# Timelapse.net
KiCad netlist of a schematic drawn in EAGLE
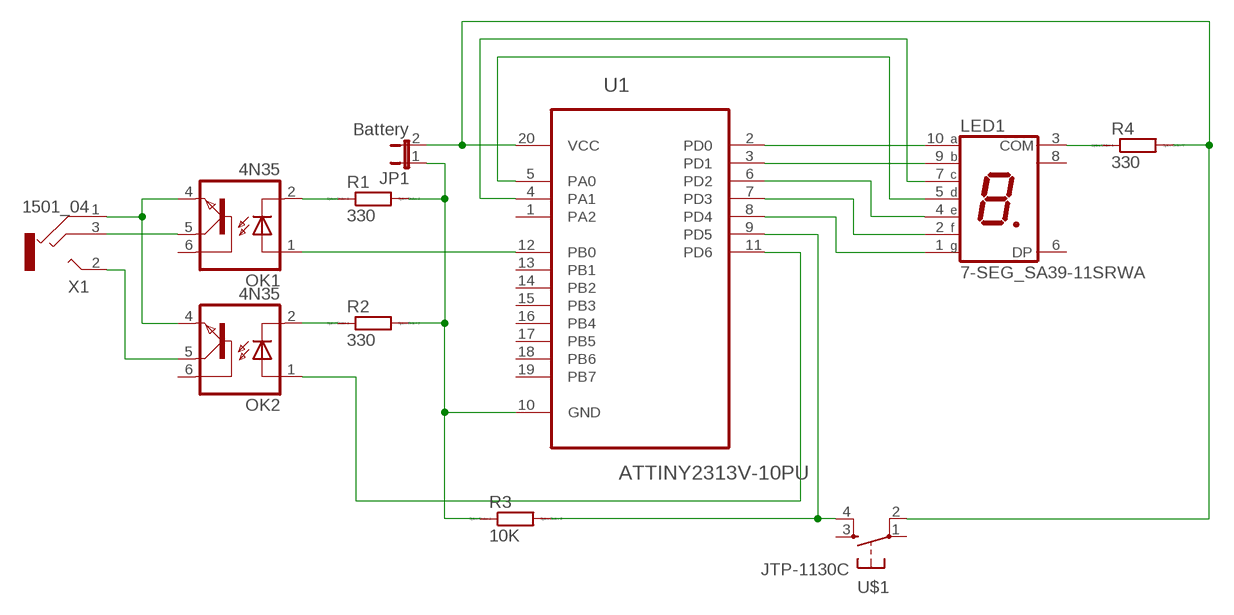
[diagram p0: schematic, sheet 1]

(export (version "E")
  (design (tool "Eeschema 10.0.6"))
  (components
    (comp (ref "JP1")
      (value "Battery")
      (footprint "eagle-import:JP1")
      (libsource (lib "eagle-import") (part "JP1E"))
    )
    (comp (ref "LED1")
      (value "7-SEG_SA39-11SRWA")
      (footprint "eagle-import:SA39-11SRWA")
      (libsource (lib "eagle-import") (part "7-SEG_SA39-11SRWA"))
    )
    (comp (ref "OK1")
      (value "4N35")
      (footprint "eagle-import:DIL06")
      (fields (field (name "MF") "FAIRCHILD SEMICONDUCTOR"))
      (libsource (lib "eagle-import") (part "4N35"))
    )
    (comp (ref "OK2")
      (value "4N35")
      (footprint "eagle-import:DIL06")
      (fields (field (name "MF") "FAIRCHILD SEMICONDUCTOR"))
      (libsource (lib "eagle-import") (part "4N35"))
    )
    (comp (ref "R1")
      (value "330")
      (footprint "eagle-import:0204_7")
      (libsource (lib "eagle-import") (part "R0204/7"))
    )
    (comp (ref "R2")
      (value "330")
      (footprint "eagle-import:0204_7")
      (libsource (lib "eagle-import") (part "R0204/7"))
    )
    (comp (ref "R3")
      (value "10K")
      (footprint "eagle-import:0204_7")
      (libsource (lib "eagle-import") (part "R0204/7"))
    )
    (comp (ref "R4")
      (value "330")
      (footprint "eagle-import:0204_7")
      (libsource (lib "eagle-import") (part "R0204/7"))
    )
    (comp (ref "U$1")
      (value "JTP-1130C")
      (footprint "eagle-import:JTP-1130")
      (libsource (lib "eagle-import") (part "JTP-1130C"))
    )
    (comp (ref "U1")
      (value "ATTINY2313V-10PU")
      (footprint "eagle-import:DIP254P762X533-20")
      (libsource (lib "eagle-import") (part "ATTINY2313V-10PU"))
    )
    (comp (ref "X1")
      (value "1501_04")
      (footprint "eagle-import:1501_05")
      (libsource (lib "eagle-import") (part "1501_04"))
    )
  )
  (nets
    (net (code "1") (name "Net-(LED1-A)") (class "Default")
      (node (ref "LED1") (pin "10") (pinfunction "A_10") (pintype "passive"))
      (node (ref "U1") (pin "2") (pinfunction "PD0_2") (pintype "bidirectional"))
    )
    (net (code "2") (name "Net-(LED1-B)") (class "Default")
      (node (ref "LED1") (pin "9") (pinfunction "B_9") (pintype "passive"))
      (node (ref "U1") (pin "3") (pinfunction "PD1_3") (pintype "bidirectional"))
    )
    (net (code "3") (name "Net-(LED1-C)") (class "Default")
      (node (ref "LED1") (pin "7") (pinfunction "C_7") (pintype "passive"))
      (node (ref "U1") (pin "4") (pinfunction "PA1_4") (pintype "bidirectional"))
    )
    (net (code "4") (name "Net-(LED1-COM-Pad3)") (class "Default")
      (node (ref "LED1") (pin "3") (pinfunction "COM_3") (pintype "passive"))
      (node (ref "R4") (pin "1") (pinfunction "1_1") (pintype "passive"))
    )
    (net (code "5") (name "Net-(LED1-D)") (class "Default")
      (node (ref "LED1") (pin "5") (pinfunction "D_5") (pintype "passive"))
      (node (ref "U1") (pin "5") (pinfunction "PA0_5") (pintype "bidirectional"))
    )
    (net (code "6") (name "Net-(LED1-E)") (class "Default")
      (node (ref "LED1") (pin "4") (pinfunction "E_4") (pintype "passive"))
      (node (ref "U1") (pin "6") (pinfunction "PD2_6") (pintype "bidirectional"))
    )
    (net (code "7") (name "Net-(LED1-F)") (class "Default")
      (node (ref "LED1") (pin "2") (pinfunction "F_2") (pintype "passive"))
      (node (ref "U1") (pin "7") (pinfunction "PD3_7") (pintype "bidirectional"))
    )
    (net (code "8") (name "Net-(LED1-G)") (class "Default")
      (node (ref "LED1") (pin "1") (pinfunction "G_1") (pintype "passive"))
      (node (ref "U1") (pin "8") (pinfunction "PD4_8") (pintype "bidirectional"))
    )
    (net (code "9") (name "Net-(OK1-A)") (class "Default")
      (node (ref "OK1") (pin "1") (pinfunction "A_1") (pintype "passive"))
      (node (ref "U1") (pin "12") (pinfunction "PB0_12") (pintype "bidirectional"))
    )
    (net (code "10") (name "Net-(OK1-C)") (class "Default")
      (node (ref "OK1") (pin "2") (pinfunction "C_2") (pintype "passive"))
      (node (ref "R1") (pin "1") (pinfunction "1_1") (pintype "passive"))
    )
    (net (code "11") (name "Net-(OK1-COL)") (class "Default")
      (node (ref "OK1") (pin "5") (pinfunction "COL_5") (pintype "passive"))
      (node (ref "X1") (pin "3") (pinfunction "3_3") (pintype "passive"))
    )
    (net (code "12") (name "Net-(OK1-EMI)") (class "Default")
      (node (ref "OK1") (pin "4") (pinfunction "EMI_4") (pintype "passive"))
      (node (ref "OK2") (pin "4") (pinfunction "EMI_4") (pintype "passive"))
      (node (ref "X1") (pin "1") (pinfunction "1_1") (pintype "passive"))
    )
    (net (code "13") (name "Net-(OK2-A)") (class "Default")
      (node (ref "OK2") (pin "1") (pinfunction "A_1") (pintype "passive"))
      (node (ref "U1") (pin "11") (pinfunction "PD6_11") (pintype "bidirectional"))
    )
    (net (code "14") (name "Net-(OK2-C)") (class "Default")
      (node (ref "OK2") (pin "2") (pinfunction "C_2") (pintype "passive"))
      (node (ref "R2") (pin "1") (pinfunction "1_1") (pintype "passive"))
    )
    (net (code "15") (name "Net-(OK2-COL)") (class "Default")
      (node (ref "OK2") (pin "5") (pinfunction "COL_5") (pintype "passive"))
      (node (ref "X1") (pin "2") (pinfunction "2_2") (pintype "passive"))
    )
    (net (code "16") (name "Net-(U$1-P1)") (class "Default")
      (node (ref "JP1") (pin "2") (pinfunction "2_2") (pintype "passive"))
      (node (ref "R4") (pin "2") (pinfunction "2_2") (pintype "passive"))
      (node (ref "U$1") (pin "2") (pinfunction "P1_2") (pintype "passive"))
      (node (ref "U1") (pin "20") (pinfunction "VCC_20") (pintype "power_in"))
    )
    (net (code "17") (name "Net-(U$1-S1)") (class "Default")
      (node (ref "R3") (pin "2") (pinfunction "2_2") (pintype "passive"))
      (node (ref "U$1") (pin "4") (pinfunction "S1_4") (pintype "passive"))
      (node (ref "U1") (pin "9") (pinfunction "PD5_9") (pintype "bidirectional"))
    )
    (net (code "18") (name "Net-(U1-GND)") (class "Default")
      (node (ref "JP1") (pin "1") (pinfunction "1_1") (pintype "passive"))
      (node (ref "R1") (pin "2") (pinfunction "2_2") (pintype "passive"))
      (node (ref "R2") (pin "2") (pinfunction "2_2") (pintype "passive"))
      (node (ref "R3") (pin "1") (pinfunction "1_1") (pintype "passive"))
      (node (ref "U1") (pin "10") (pinfunction "GND_10") (pintype "passive"))
    )
    (net (code "19") (name "unconnected-(LED1-COM-Pad8)") (class "Default")
      (node (ref "LED1") (pin "8") (pinfunction "COM_8") (pintype "passive"))
    )
    (net (code "20") (name "unconnected-(LED1-DP-Pad6)") (class "Default")
      (node (ref "LED1") (pin "6") (pinfunction "DP_6") (pintype "passive"))
    )
    (net (code "21") (name "unconnected-(OK1-BAS-Pad6)") (class "Default")
      (node (ref "OK1") (pin "6") (pinfunction "BAS_6") (pintype "passive"))
    )
    (net (code "22") (name "unconnected-(OK2-BAS-Pad6)") (class "Default")
      (node (ref "OK2") (pin "6") (pinfunction "BAS_6") (pintype "passive"))
    )
    (net (code "23") (name "unconnected-(U$1-P-Pad1)") (class "Default")
      (node (ref "U$1") (pin "1") (pinfunction "P_1") (pintype "passive"))
    )
    (net (code "24") (name "unconnected-(U$1-S-Pad3)") (class "Default")
      (node (ref "U$1") (pin "3") (pinfunction "S_3") (pintype "passive"))
    )
    (net (code "25") (name "unconnected-(U1-PA2-Pad1)") (class "Default")
      (node (ref "U1") (pin "1") (pinfunction "PA2_1") (pintype "bidirectional"))
    )
    (net (code "26") (name "unconnected-(U1-PB1-Pad13)") (class "Default")
      (node (ref "U1") (pin "13") (pinfunction "PB1_13") (pintype "bidirectional"))
    )
    (net (code "27") (name "unconnected-(U1-PB2-Pad14)") (class "Default")
      (node (ref "U1") (pin "14") (pinfunction "PB2_14") (pintype "bidirectional"))
    )
    (net (code "28") (name "unconnected-(U1-PB3-Pad15)") (class "Default")
      (node (ref "U1") (pin "15") (pinfunction "PB3_15") (pintype "bidirectional"))
    )
    (net (code "29") (name "unconnected-(U1-PB4-Pad16)") (class "Default")
      (node (ref "U1") (pin "16") (pinfunction "PB4_16") (pintype "bidirectional"))
    )
    (net (code "30") (name "unconnected-(U1-PB5-Pad17)") (class "Default")
      (node (ref "U1") (pin "17") (pinfunction "PB5_17") (pintype "bidirectional"))
    )
    (net (code "31") (name "unconnected-(U1-PB6-Pad18)") (class "Default")
      (node (ref "U1") (pin "18") (pinfunction "PB6_18") (pintype "bidirectional"))
    )
    (net (code "32") (name "unconnected-(U1-PB7-Pad19)") (class "Default")
      (node (ref "U1") (pin "19") (pinfunction "PB7_19") (pintype "bidirectional"))
    )
  )
)
